# Din24xOLD.net
KiCad netlist of a schematic drawn in Altium Designer
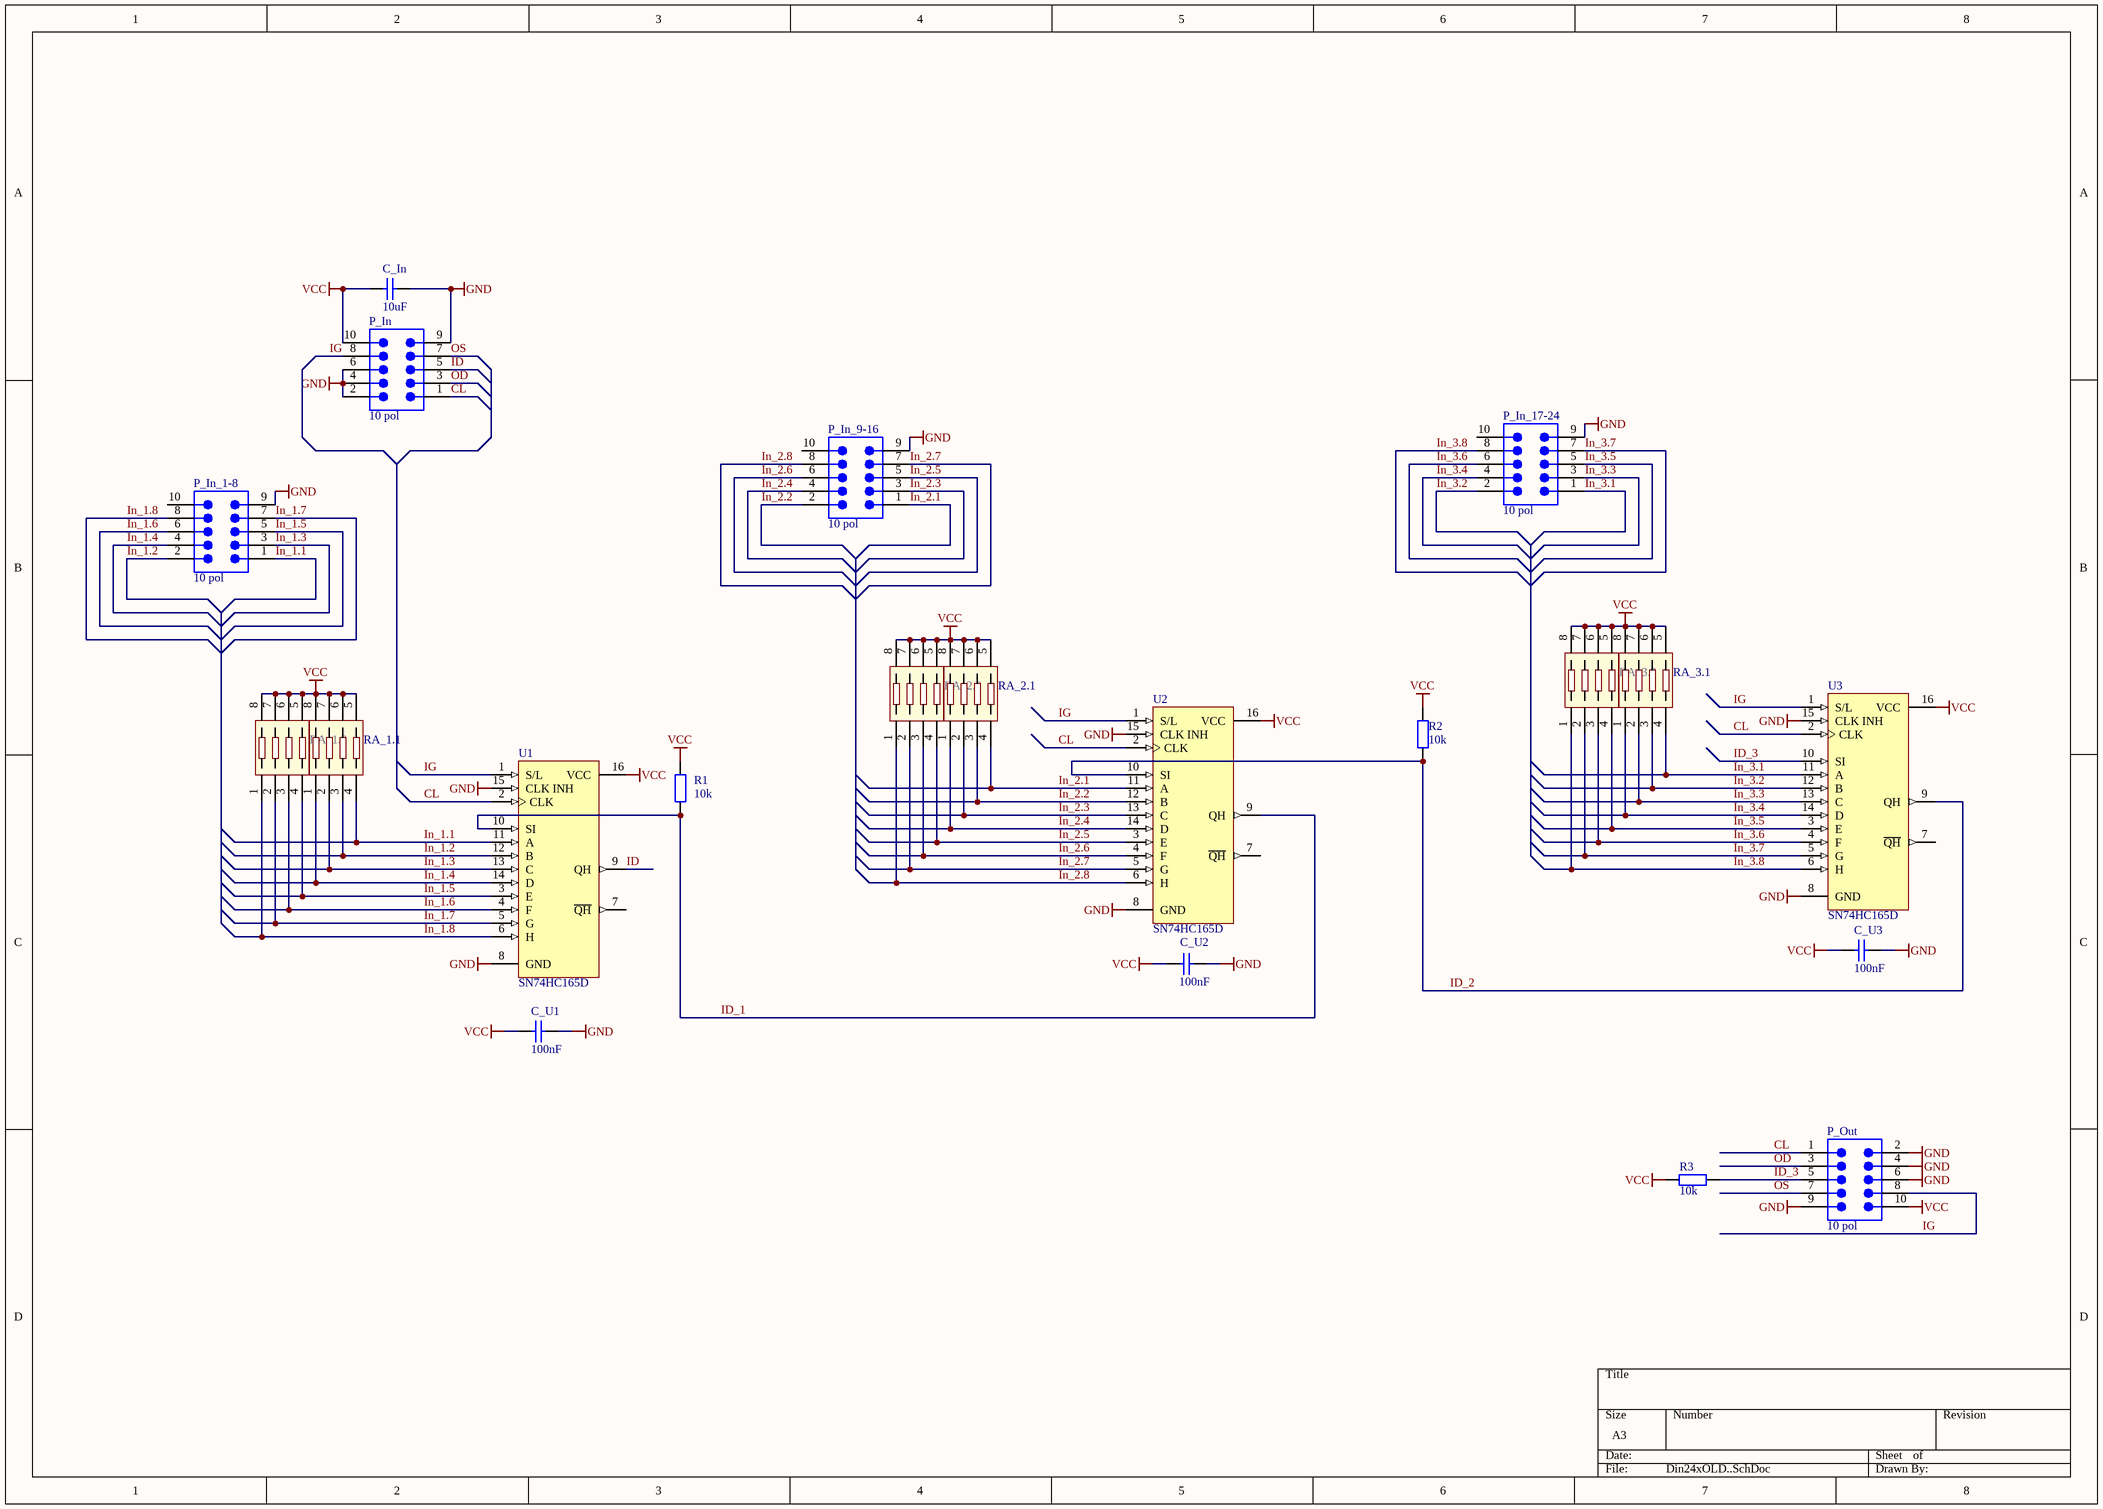
[diagram p0: Din24xOLD..SchDoc]

(export (version "E")
  (design (tool "Eeschema 10.0.6"))
  (components
    (comp (ref "C_In")
      (value "10uF")
      (footprint "1608[0603]")
      (description "Capacitor (Semiconductor SIM Model)")
      (fields (field (name "Comment") "Cap Semi") (field (name "PUBLISHER") "Altium Limited"))
      (libsource (lib "Miscellaneous Devices") (part "Cap Semi"))
    )
    (comp (ref "C_U1")
      (value "100nF")
      (footprint "1608[0603]")
      (description "Capacitor (Semiconductor SIM Model)")
      (fields (field (name "Comment") "Cap Semi") (field (name "PUBLISHER") "Altium Limited"))
      (libsource (lib "Miscellaneous Devices") (part "Cap Semi"))
    )
    (comp (ref "C_U2")
      (value "100nF")
      (footprint "1608[0603]")
      (description "Capacitor (Semiconductor SIM Model)")
      (fields (field (name "Comment") "Cap Semi") (field (name "PUBLISHER") "Altium Limited"))
      (libsource (lib "Miscellaneous Devices") (part "Cap Semi"))
    )
    (comp (ref "C_U3")
      (value "100nF")
      (footprint "1608[0603]")
      (description "Capacitor (Semiconductor SIM Model)")
      (fields (field (name "Comment") "Cap Semi") (field (name "PUBLISHER") "Altium Limited"))
      (libsource (lib "Miscellaneous Devices") (part "Cap Semi"))
    )
    (comp (ref "P_In")
      (value "10 pol")
      (footprint "918510x324")
      (fields (field (name "PUBLISHER") "Altium Limited"))
      (libsource (lib "HARTING IDC 2.54mm Pitch") (part "09 18 510 6324"))
    )
    (comp (ref "P_In_1-8")
      (value "10 pol")
      (footprint "918510x324")
      (fields (field (name "PUBLISHER") "Altium Limited"))
      (libsource (lib "HARTING IDC 2.54mm Pitch") (part "09 18 510 6324"))
    )
    (comp (ref "P_In_9-16")
      (value "10 pol")
      (footprint "918510x324")
      (fields (field (name "PUBLISHER") "Altium Limited"))
      (libsource (lib "HARTING IDC 2.54mm Pitch") (part "09 18 510 6324"))
    )
    (comp (ref "P_In_17-24")
      (value "10 pol")
      (footprint "918510x324")
      (fields (field (name "PUBLISHER") "Altium Limited"))
      (libsource (lib "HARTING IDC 2.54mm Pitch") (part "09 18 510 6324"))
    )
    (comp (ref "P_Out")
      (value "10 pol")
      (footprint "918510x324")
      (fields (field (name "PUBLISHER") "Altium Limited"))
      (libsource (lib "") (part "09 18 510 6324_1"))
    )
    (comp (ref "R1")
      (value "10k")
      (footprint "1608[0603]")
      (description "Resistor")
      (fields (field (name "Comment") "Res2") (field (name "PUBLISHER") "Altium Limited"))
      (libsource (lib "") (part "Res2_1"))
    )
    (comp (ref "R2")
      (value "10k")
      (footprint "1608[0603]")
      (description "Resistor")
      (fields (field (name "Comment") "Res2") (field (name "PUBLISHER") "Altium Limited"))
      (libsource (lib "") (part "Res2_1"))
    )
    (comp (ref "R3")
      (value "10k")
      (footprint "1608[0603]")
      (description "Resistor")
      (fields (field (name "Comment") "Res2") (field (name "PUBLISHER") "Altium Limited"))
      (libsource (lib "Miscellaneous Devices") (part "Res2"))
    )
    (comp (ref "RA_1.1")
      (value "EXB38")
      (footprint "Panasonic EXB38V:EXB38")
      (fields (field (name "PUBLISHER") "Altium Limited"))
      (libsource (lib "Panasonic Resistor Array") (part "4 Resistors Parallel"))
    )
    (comp (ref "RA_1.2")
      (value "EXB38")
      (footprint "Panasonic EXB38V:EXB38")
      (fields (field (name "PUBLISHER") "Altium Limited"))
      (libsource (lib "Panasonic Resistor Array") (part "4 Resistors Parallel"))
    )
    (comp (ref "RA_2.1")
      (value "EXB38")
      (footprint "Panasonic EXB38V:EXB38")
      (fields (field (name "PUBLISHER") "Altium Limited"))
      (libsource (lib "Panasonic Resistor Array") (part "4 Resistors Parallel"))
    )
    (comp (ref "RA_2.2")
      (value "EXB38")
      (footprint "Panasonic EXB38V:EXB38")
      (fields (field (name "PUBLISHER") "Altium Limited"))
      (libsource (lib "Panasonic Resistor Array") (part "4 Resistors Parallel"))
    )
    (comp (ref "RA_3.1")
      (value "EXB38")
      (footprint "Panasonic EXB38V:EXB38")
      (fields (field (name "PUBLISHER") "Altium Limited"))
      (libsource (lib "Panasonic Resistor Array") (part "4 Resistors Parallel"))
    )
    (comp (ref "RA_3.2")
      (value "EXB38")
      (footprint "Panasonic EXB38V:EXB38")
      (fields (field (name "PUBLISHER") "Altium Limited"))
      (libsource (lib "Panasonic Resistor Array") (part "4 Resistors Parallel"))
    )
    (comp (ref "U1")
      (value "SN74HC165D")
      (footprint "D016_L")
      (description "8-Bit Parallel-Load Shift Register")
      (fields (field (name "PUBLISHER") "Altium Limited"))
      (libsource (lib "TI Logic Register") (part "SN74HC165D"))
    )
    (comp (ref "U2")
      (value "SN74HC165D")
      (footprint "D016_L")
      (description "8-Bit Parallel-Load Shift Register")
      (fields (field (name "PUBLISHER") "Altium Limited"))
      (libsource (lib "TI Logic Register") (part "SN74HC165D"))
    )
    (comp (ref "U3")
      (value "SN74HC165D")
      (footprint "D016_L")
      (description "8-Bit Parallel-Load Shift Register")
      (fields (field (name "PUBLISHER") "Altium Limited"))
      (libsource (lib "TI Logic Register") (part "SN74HC165D"))
    )
  )
  (nets
    (net (code "1") (name "/CL") (class "Default")
      (node (ref "P_In") (pin "1") (pinfunction "1_1") (pintype "passive"))
      (node (ref "P_Out") (pin "1") (pinfunction "1_1") (pintype "passive"))
      (node (ref "U1") (pin "2") (pinfunction "CLK_2") (pintype "input"))
      (node (ref "U2") (pin "2") (pinfunction "CLK_2") (pintype "input"))
      (node (ref "U3") (pin "2") (pinfunction "CLK_2") (pintype "input"))
    )
    (net (code "2") (name "/ID") (class "Default")
      (node (ref "P_In") (pin "5") (pinfunction "5_5") (pintype "passive"))
      (node (ref "U1") (pin "9") (pinfunction "QH_9") (pintype "output"))
    )
    (net (code "3") (name "/ID_1") (class "Default")
      (node (ref "R1") (pin "1") (pinfunction "1_1") (pintype "passive"))
      (node (ref "U1") (pin "10") (pinfunction "SI_10") (pintype "input"))
      (node (ref "U2") (pin "9") (pinfunction "QH_9") (pintype "output"))
    )
    (net (code "4") (name "/ID_2") (class "Default")
      (node (ref "R2") (pin "1") (pinfunction "1_1") (pintype "passive"))
      (node (ref "U2") (pin "10") (pinfunction "SI_10") (pintype "input"))
      (node (ref "U3") (pin "9") (pinfunction "QH_9") (pintype "output"))
    )
    (net (code "5") (name "/ID_3") (class "Default")
      (node (ref "P_Out") (pin "5") (pinfunction "5_5") (pintype "passive"))
      (node (ref "R3") (pin "1") (pinfunction "1_1") (pintype "passive"))
      (node (ref "U3") (pin "10") (pinfunction "SI_10") (pintype "input"))
    )
    (net (code "6") (name "/IG") (class "Default")
      (node (ref "P_In") (pin "8") (pinfunction "8_8") (pintype "passive"))
      (node (ref "P_Out") (pin "8") (pinfunction "8_8") (pintype "passive"))
      (node (ref "U1") (pin "1") (pinfunction "S/L_1") (pintype "input"))
      (node (ref "U2") (pin "1") (pinfunction "S/L_1") (pintype "input"))
      (node (ref "U3") (pin "1") (pinfunction "S/L_1") (pintype "input"))
    )
    (net (code "7") (name "/In_1.1") (class "Default")
      (node (ref "P_In_1-8") (pin "1") (pinfunction "1_1") (pintype "passive"))
      (node (ref "RA_1.1") (pin "4") (pinfunction "4_4") (pintype "passive"))
      (node (ref "U1") (pin "11") (pinfunction "A_11") (pintype "input"))
    )
    (net (code "8") (name "/In_1.2") (class "Default")
      (node (ref "P_In_1-8") (pin "2") (pinfunction "2_2") (pintype "passive"))
      (node (ref "RA_1.1") (pin "3") (pinfunction "3_3") (pintype "passive"))
      (node (ref "U1") (pin "12") (pinfunction "B_12") (pintype "input"))
    )
    (net (code "9") (name "/In_1.3") (class "Default")
      (node (ref "P_In_1-8") (pin "3") (pinfunction "3_3") (pintype "passive"))
      (node (ref "RA_1.1") (pin "2") (pinfunction "2_2") (pintype "passive"))
      (node (ref "U1") (pin "13") (pinfunction "C_13") (pintype "input"))
    )
    (net (code "10") (name "/In_1.4") (class "Default")
      (node (ref "P_In_1-8") (pin "4") (pinfunction "4_4") (pintype "passive"))
      (node (ref "RA_1.1") (pin "1") (pinfunction "1_1") (pintype "passive"))
      (node (ref "U1") (pin "14") (pinfunction "D_14") (pintype "input"))
    )
    (net (code "11") (name "/In_1.5") (class "Default")
      (node (ref "P_In_1-8") (pin "5") (pinfunction "5_5") (pintype "passive"))
      (node (ref "RA_1.2") (pin "4") (pinfunction "4_4") (pintype "passive"))
      (node (ref "U1") (pin "3") (pinfunction "E_3") (pintype "input"))
    )
    (net (code "12") (name "/In_1.6") (class "Default")
      (node (ref "P_In_1-8") (pin "6") (pinfunction "6_6") (pintype "passive"))
      (node (ref "RA_1.2") (pin "3") (pinfunction "3_3") (pintype "passive"))
      (node (ref "U1") (pin "4") (pinfunction "F_4") (pintype "input"))
    )
    (net (code "13") (name "/In_1.7") (class "Default")
      (node (ref "P_In_1-8") (pin "7") (pinfunction "7_7") (pintype "passive"))
      (node (ref "RA_1.2") (pin "2") (pinfunction "2_2") (pintype "passive"))
      (node (ref "U1") (pin "5") (pinfunction "G_5") (pintype "input"))
    )
    (net (code "14") (name "/In_1.8") (class "Default")
      (node (ref "P_In_1-8") (pin "8") (pinfunction "8_8") (pintype "passive"))
      (node (ref "RA_1.2") (pin "1") (pinfunction "1_1") (pintype "passive"))
      (node (ref "U1") (pin "6") (pinfunction "H_6") (pintype "input"))
    )
    (net (code "15") (name "/In_2.1") (class "Default")
      (node (ref "P_In_9-16") (pin "1") (pinfunction "1_1") (pintype "passive"))
      (node (ref "RA_2.1") (pin "4") (pinfunction "4_4") (pintype "passive"))
      (node (ref "U2") (pin "11") (pinfunction "A_11") (pintype "input"))
    )
    (net (code "16") (name "/In_2.2") (class "Default")
      (node (ref "P_In_9-16") (pin "2") (pinfunction "2_2") (pintype "passive"))
      (node (ref "RA_2.1") (pin "3") (pinfunction "3_3") (pintype "passive"))
      (node (ref "U2") (pin "12") (pinfunction "B_12") (pintype "input"))
    )
    (net (code "17") (name "/In_2.3") (class "Default")
      (node (ref "P_In_9-16") (pin "3") (pinfunction "3_3") (pintype "passive"))
      (node (ref "RA_2.1") (pin "2") (pinfunction "2_2") (pintype "passive"))
      (node (ref "U2") (pin "13") (pinfunction "C_13") (pintype "input"))
    )
    (net (code "18") (name "/In_2.4") (class "Default")
      (node (ref "P_In_9-16") (pin "4") (pinfunction "4_4") (pintype "passive"))
      (node (ref "RA_2.1") (pin "1") (pinfunction "1_1") (pintype "passive"))
      (node (ref "U2") (pin "14") (pinfunction "D_14") (pintype "input"))
    )
    (net (code "19") (name "/In_2.5") (class "Default")
      (node (ref "P_In_9-16") (pin "5") (pinfunction "5_5") (pintype "passive"))
      (node (ref "RA_2.2") (pin "4") (pinfunction "4_4") (pintype "passive"))
      (node (ref "U2") (pin "3") (pinfunction "E_3") (pintype "input"))
    )
    (net (code "20") (name "/In_2.6") (class "Default")
      (node (ref "P_In_9-16") (pin "6") (pinfunction "6_6") (pintype "passive"))
      (node (ref "RA_2.2") (pin "3") (pinfunction "3_3") (pintype "passive"))
      (node (ref "U2") (pin "4") (pinfunction "F_4") (pintype "input"))
    )
    (net (code "21") (name "/In_2.7") (class "Default")
      (node (ref "P_In_9-16") (pin "7") (pinfunction "7_7") (pintype "passive"))
      (node (ref "RA_2.2") (pin "2") (pinfunction "2_2") (pintype "passive"))
      (node (ref "U2") (pin "5") (pinfunction "G_5") (pintype "input"))
    )
    (net (code "22") (name "/In_2.8") (class "Default")
      (node (ref "P_In_9-16") (pin "8") (pinfunction "8_8") (pintype "passive"))
      (node (ref "RA_2.2") (pin "1") (pinfunction "1_1") (pintype "passive"))
      (node (ref "U2") (pin "6") (pinfunction "H_6") (pintype "input"))
    )
    (net (code "23") (name "/In_3.1") (class "Default")
      (node (ref "P_In_17-24") (pin "1") (pinfunction "1_1") (pintype "passive"))
      (node (ref "RA_3.1") (pin "4") (pinfunction "4_4") (pintype "passive"))
      (node (ref "U3") (pin "11") (pinfunction "A_11") (pintype "input"))
    )
    (net (code "24") (name "/In_3.2") (class "Default")
      (node (ref "P_In_17-24") (pin "2") (pinfunction "2_2") (pintype "passive"))
      (node (ref "RA_3.1") (pin "3") (pinfunction "3_3") (pintype "passive"))
      (node (ref "U3") (pin "12") (pinfunction "B_12") (pintype "input"))
    )
    (net (code "25") (name "/In_3.3") (class "Default")
      (node (ref "P_In_17-24") (pin "3") (pinfunction "3_3") (pintype "passive"))
      (node (ref "RA_3.1") (pin "2") (pinfunction "2_2") (pintype "passive"))
      (node (ref "U3") (pin "13") (pinfunction "C_13") (pintype "input"))
    )
    (net (code "26") (name "/In_3.4") (class "Default")
      (node (ref "P_In_17-24") (pin "4") (pinfunction "4_4") (pintype "passive"))
      (node (ref "RA_3.1") (pin "1") (pinfunction "1_1") (pintype "passive"))
      (node (ref "U3") (pin "14") (pinfunction "D_14") (pintype "input"))
    )
    (net (code "27") (name "/In_3.5") (class "Default")
      (node (ref "P_In_17-24") (pin "5") (pinfunction "5_5") (pintype "passive"))
      (node (ref "RA_3.2") (pin "4") (pinfunction "4_4") (pintype "passive"))
      (node (ref "U3") (pin "3") (pinfunction "E_3") (pintype "input"))
    )
    (net (code "28") (name "/In_3.6") (class "Default")
      (node (ref "P_In_17-24") (pin "6") (pinfunction "6_6") (pintype "passive"))
      (node (ref "RA_3.2") (pin "3") (pinfunction "3_3") (pintype "passive"))
      (node (ref "U3") (pin "4") (pinfunction "F_4") (pintype "input"))
    )
    (net (code "29") (name "/In_3.7") (class "Default")
      (node (ref "P_In_17-24") (pin "7") (pinfunction "7_7") (pintype "passive"))
      (node (ref "RA_3.2") (pin "2") (pinfunction "2_2") (pintype "passive"))
      (node (ref "U3") (pin "5") (pinfunction "G_5") (pintype "input"))
    )
    (net (code "30") (name "/In_3.8") (class "Default")
      (node (ref "P_In_17-24") (pin "8") (pinfunction "8_8") (pintype "passive"))
      (node (ref "RA_3.2") (pin "1") (pinfunction "1_1") (pintype "passive"))
      (node (ref "U3") (pin "6") (pinfunction "H_6") (pintype "input"))
    )
    (net (code "31") (name "/OD") (class "Default")
      (node (ref "P_In") (pin "3") (pinfunction "3_3") (pintype "passive"))
      (node (ref "P_Out") (pin "3") (pinfunction "3_3") (pintype "passive"))
    )
    (net (code "32") (name "/OS") (class "Default")
      (node (ref "P_In") (pin "7") (pinfunction "7_7") (pintype "passive"))
      (node (ref "P_Out") (pin "7") (pinfunction "7_7") (pintype "passive"))
    )
    (net (code "33") (name "GND") (class "Default")
      (node (ref "C_In") (pin "1") (pinfunction "1_1") (pintype "passive"))
      (node (ref "C_U1") (pin "1") (pinfunction "1_1") (pintype "passive"))
      (node (ref "C_U2") (pin "1") (pinfunction "1_1") (pintype "passive"))
      (node (ref "C_U3") (pin "1") (pinfunction "1_1") (pintype "passive"))
      (node (ref "P_In") (pin "2") (pinfunction "2_2") (pintype "passive"))
      (node (ref "P_In") (pin "4") (pinfunction "4_4") (pintype "passive"))
      (node (ref "P_In") (pin "6") (pinfunction "6_6") (pintype "passive"))
      (node (ref "P_In") (pin "9") (pinfunction "9_9") (pintype "passive"))
      (node (ref "P_In_1-8") (pin "9") (pinfunction "9_9") (pintype "passive"))
      (node (ref "P_In_17-24") (pin "9") (pinfunction "9_9") (pintype "passive"))
      (node (ref "P_In_9-16") (pin "9") (pinfunction "9_9") (pintype "passive"))
      (node (ref "P_Out") (pin "2") (pinfunction "2_2") (pintype "passive"))
      (node (ref "P_Out") (pin "4") (pinfunction "4_4") (pintype "passive"))
      (node (ref "P_Out") (pin "6") (pinfunction "6_6") (pintype "passive"))
      (node (ref "P_Out") (pin "9") (pinfunction "9_9") (pintype "passive"))
      (node (ref "U1") (pin "15") (pinfunction "CLK_INH_15") (pintype "input"))
      (node (ref "U1") (pin "8") (pinfunction "GND_8") (pintype "power_in"))
      (node (ref "U2") (pin "15") (pinfunction "CLK_INH_15") (pintype "input"))
      (node (ref "U2") (pin "8") (pinfunction "GND_8") (pintype "power_in"))
      (node (ref "U3") (pin "15") (pinfunction "CLK_INH_15") (pintype "input"))
      (node (ref "U3") (pin "8") (pinfunction "GND_8") (pintype "power_in"))
    )
    (net (code "34") (name "VCC") (class "Default")
      (node (ref "C_In") (pin "2") (pinfunction "2_2") (pintype "passive"))
      (node (ref "C_U1") (pin "2") (pinfunction "2_2") (pintype "passive"))
      (node (ref "C_U2") (pin "2") (pinfunction "2_2") (pintype "passive"))
      (node (ref "C_U3") (pin "2") (pinfunction "2_2") (pintype "passive"))
      (node (ref "P_In") (pin "10") (pinfunction "10_10") (pintype "passive"))
      (node (ref "P_Out") (pin "10") (pinfunction "10_10") (pintype "passive"))
      (node (ref "R1") (pin "2") (pinfunction "2_2") (pintype "passive"))
      (node (ref "R2") (pin "2") (pinfunction "2_2") (pintype "passive"))
      (node (ref "R3") (pin "2") (pinfunction "2_2") (pintype "passive"))
      (node (ref "RA_1.1") (pin "5") (pinfunction "5_5") (pintype "passive"))
      (node (ref "RA_1.1") (pin "6") (pinfunction "6_6") (pintype "passive"))
      (node (ref "RA_1.1") (pin "7") (pinfunction "7_7") (pintype "passive"))
      (node (ref "RA_1.1") (pin "8") (pinfunction "8_8") (pintype "passive"))
      (node (ref "RA_1.2") (pin "5") (pinfunction "5_5") (pintype "passive"))
      (node (ref "RA_1.2") (pin "6") (pinfunction "6_6") (pintype "passive"))
      (node (ref "RA_1.2") (pin "7") (pinfunction "7_7") (pintype "passive"))
      (node (ref "RA_1.2") (pin "8") (pinfunction "8_8") (pintype "passive"))
      (node (ref "RA_2.1") (pin "5") (pinfunction "5_5") (pintype "passive"))
      (node (ref "RA_2.1") (pin "6") (pinfunction "6_6") (pintype "passive"))
      (node (ref "RA_2.1") (pin "7") (pinfunction "7_7") (pintype "passive"))
      (node (ref "RA_2.1") (pin "8") (pinfunction "8_8") (pintype "passive"))
      (node (ref "RA_2.2") (pin "5") (pinfunction "5_5") (pintype "passive"))
      (node (ref "RA_2.2") (pin "6") (pinfunction "6_6") (pintype "passive"))
      (node (ref "RA_2.2") (pin "7") (pinfunction "7_7") (pintype "passive"))
      (node (ref "RA_2.2") (pin "8") (pinfunction "8_8") (pintype "passive"))
      (node (ref "RA_3.1") (pin "5") (pinfunction "5_5") (pintype "passive"))
      (node (ref "RA_3.1") (pin "6") (pinfunction "6_6") (pintype "passive"))
      (node (ref "RA_3.1") (pin "7") (pinfunction "7_7") (pintype "passive"))
      (node (ref "RA_3.1") (pin "8") (pinfunction "8_8") (pintype "passive"))
      (node (ref "RA_3.2") (pin "5") (pinfunction "5_5") (pintype "passive"))
      (node (ref "RA_3.2") (pin "6") (pinfunction "6_6") (pintype "passive"))
      (node (ref "RA_3.2") (pin "7") (pinfunction "7_7") (pintype "passive"))
      (node (ref "RA_3.2") (pin "8") (pinfunction "8_8") (pintype "passive"))
      (node (ref "U1") (pin "16") (pinfunction "VCC_16") (pintype "power_in"))
      (node (ref "U2") (pin "16") (pinfunction "VCC_16") (pintype "power_in"))
      (node (ref "U3") (pin "16") (pinfunction "VCC_16") (pintype "power_in"))
    )
    (net (code "35") (name "unconnected-(P_In_1-8-Pad10)") (class "Default")
      (node (ref "P_In_1-8") (pin "10") (pinfunction "10_10") (pintype "passive"))
    )
    (net (code "36") (name "unconnected-(P_In_9-16-Pad10)") (class "Default")
      (node (ref "P_In_9-16") (pin "10") (pinfunction "10_10") (pintype "passive"))
    )
    (net (code "37") (name "unconnected-(P_In_17-24-Pad10)") (class "Default")
      (node (ref "P_In_17-24") (pin "10") (pinfunction "10_10") (pintype "passive"))
    )
    (net (code "38") (name "unconnected-(U1-~{QH}-Pad7)") (class "Default")
      (node (ref "U1") (pin "7") (pinfunction "~{QH}_7") (pintype "output"))
    )
    (net (code "39") (name "unconnected-(U2-~{QH}-Pad7)") (class "Default")
      (node (ref "U2") (pin "7") (pinfunction "~{QH}_7") (pintype "output"))
    )
    (net (code "40") (name "unconnected-(U3-~{QH}-Pad7)") (class "Default")
      (node (ref "U3") (pin "7") (pinfunction "~{QH}_7") (pintype "output"))
    )
  )
)
